# Arduino_UNO_schematic.net
KiCad netlist of a schematic drawn in Altium Designer
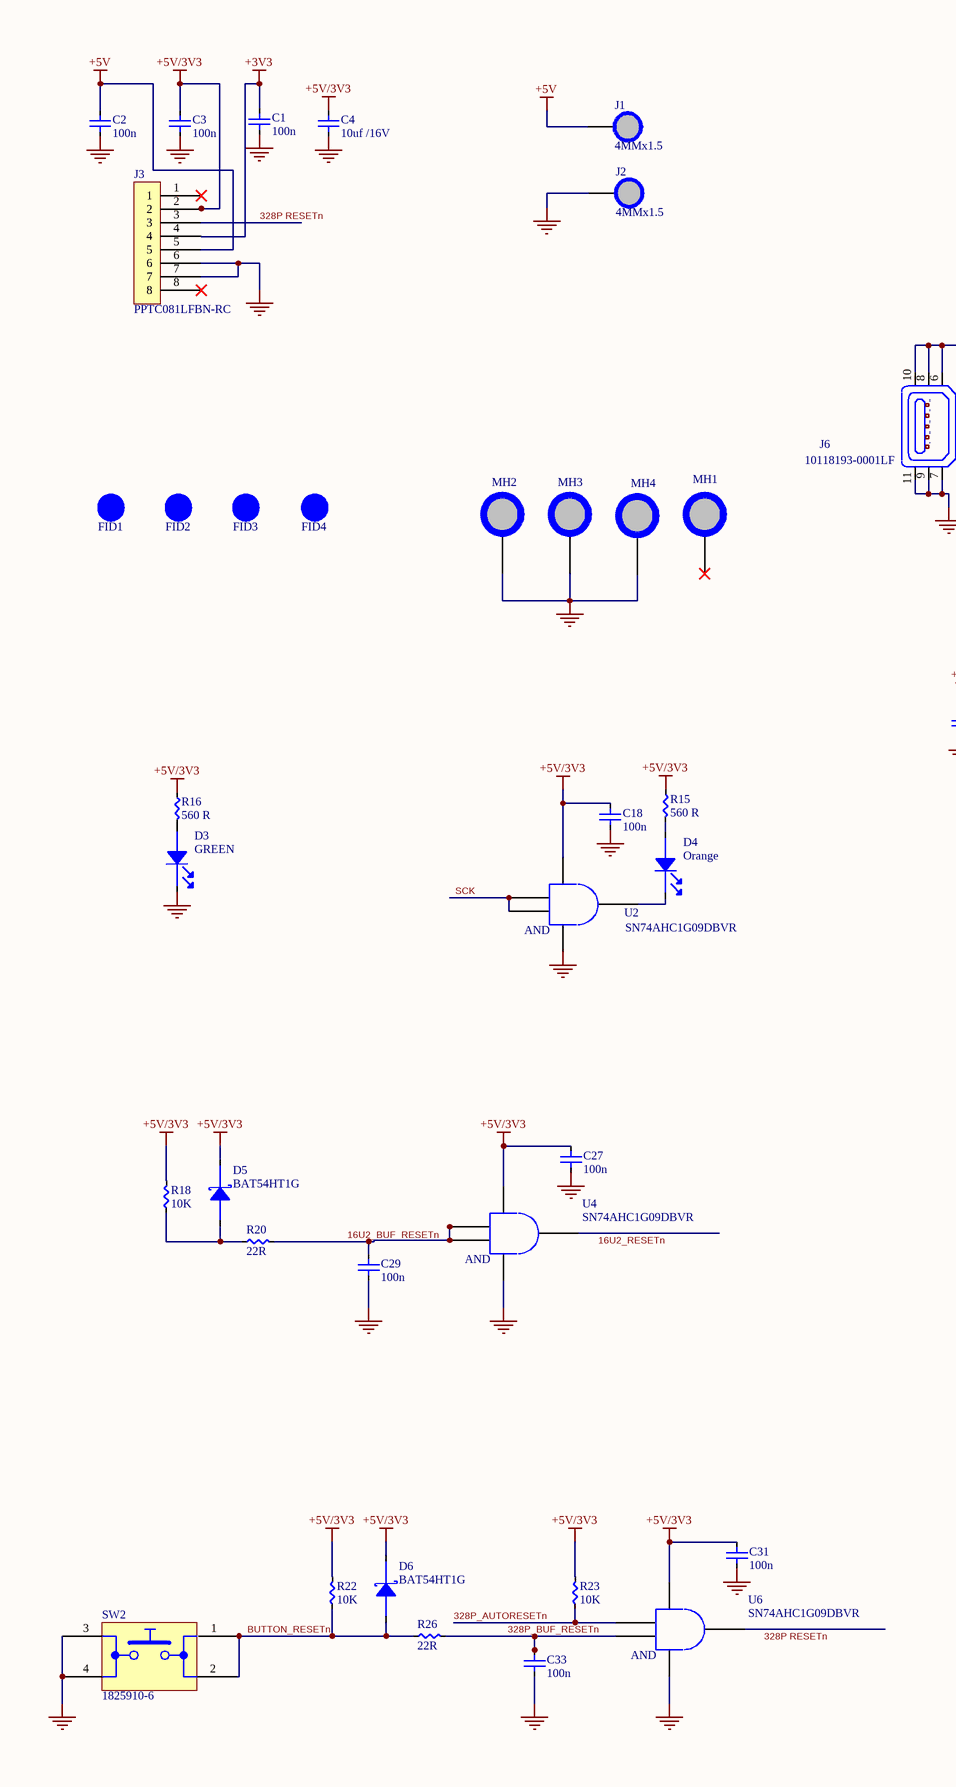
[diagram p0: Arduino_UNO_schematic.SchDoc, left]
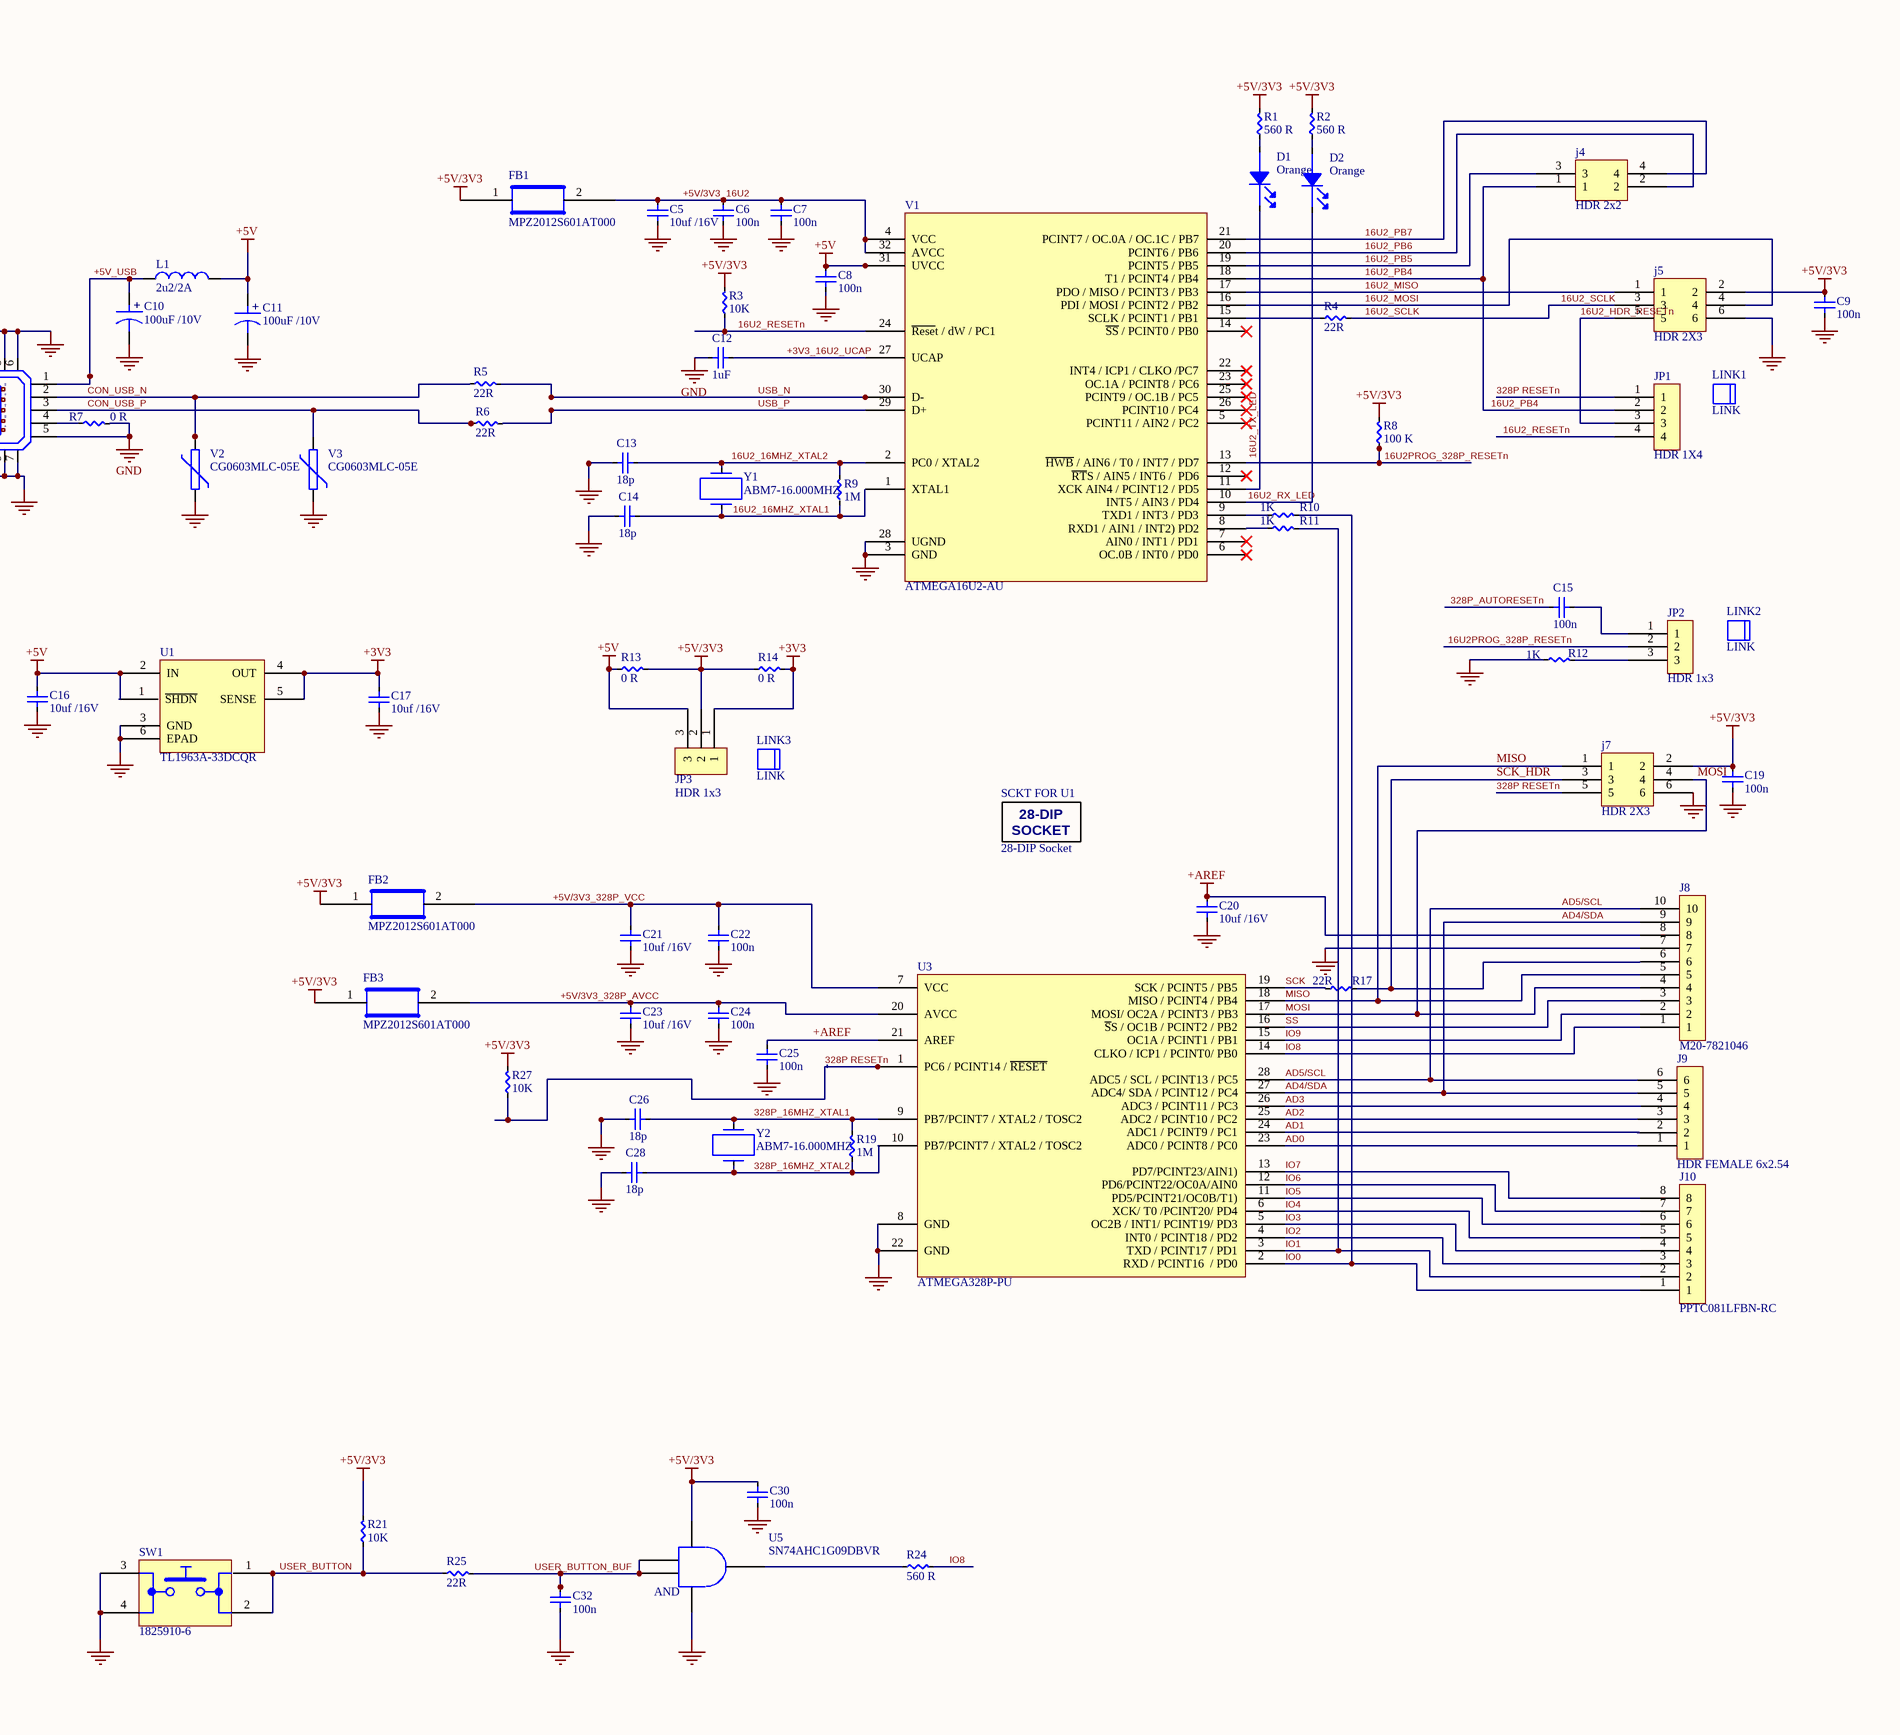
[diagram p1: Arduino_UNO_schematic.SchDoc, right]

(export (version "E")
  (design (tool "Eeschema 10.0.6"))
  (components
    (comp (ref "C1")
      (value "100n")
      (footprint "C805")
      (description "Cap Ceramic 0.1uF 50V X7R 20% SMD 0805 125°C Punched Paper T/R")
      (fields (field (name "TOLERANCE") "20%") (field (name "MANUFACTURER") "KEMET"))
      (libsource (lib "Arduino_UNO_Schematic_lib") (part "C0805C104M5RACAUTO"))
    )
    (comp (ref "C2")
      (value "100n")
      (footprint "C805")
      (description "Cap Ceramic 0.1uF 50V X7R 20% SMD 0805 125°C Punched Paper T/R")
      (fields (field (name "TOLERANCE") "20%") (field (name "MANUFACTURER") "KEMET"))
      (libsource (lib "Arduino_UNO_Schematic_lib") (part "C0805C104M5RACAUTO"))
    )
    (comp (ref "C3")
      (value "100n")
      (footprint "C805")
      (description "Cap Ceramic 0.1uF 50V X7R 20% SMD 0805 125°C Punched Paper T/R")
      (fields (field (name "TOLERANCE") "20%") (field (name "MANUFACTURER") "KEMET"))
      (libsource (lib "Arduino_UNO_Schematic_lib") (part "C0805C104M5RACAUTO"))
    )
    (comp (ref "C4")
      (value "10uf /16V")
      (footprint "C805-10Uf")
      (description "TDK - CGA4J1X7S1C106K125AC - CGA4J1X7S1C106KT000N")
      (fields
        (field (name "TOLERANCE") "10%")
        (field (name "MANUFACTURER PART NUMBER") "CGA4J1X7S1C106K125AC")
      )
      (libsource (lib "Arduino_UNO_Schematic_lib") (part "CGA4J1X7S1C106K125AC"))
    )
    (comp (ref "C5")
      (value "10uf /16V")
      (footprint "C805-10Uf")
      (description "TDK - CGA4J1X7S1C106K125AC - CGA4J1X7S1C106KT000N")
      (fields
        (field (name "TOLERANCE") "10%")
        (field (name "MANUFACTURER PART NUMBER") "CGA4J1X7S1C106K125AC")
      )
      (libsource (lib "Arduino_UNO_Schematic_lib") (part "CGA4J1X7S1C106K125AC"))
    )
    (comp (ref "C6")
      (value "100n")
      (footprint "C805")
      (description "Cap Ceramic 0.1uF 50V X7R 20% SMD 0805 125°C Punched Paper T/R")
      (fields (field (name "TOLERANCE") "20%") (field (name "MANUFACTURER") "KEMET"))
      (libsource (lib "Arduino_UNO_Schematic_lib") (part "C0805C104M5RACAUTO"))
    )
    (comp (ref "C7")
      (value "100n")
      (footprint "C805")
      (description "Cap Ceramic 0.1uF 50V X7R 20% SMD 0805 125°C Punched Paper T/R")
      (fields (field (name "TOLERANCE") "20%") (field (name "MANUFACTURER") "KEMET"))
      (libsource (lib "Arduino_UNO_Schematic_lib") (part "C0805C104M5RACAUTO"))
    )
    (comp (ref "C8")
      (value "100n")
      (footprint "C805")
      (description "Cap Ceramic 0.1uF 50V X7R 20% SMD 0805 125°C Punched Paper T/R")
      (fields (field (name "TOLERANCE") "20%") (field (name "MANUFACTURER") "KEMET"))
      (libsource (lib "Arduino_UNO_Schematic_lib") (part "C0805C104M5RACAUTO"))
    )
    (comp (ref "C9")
      (value "100n")
      (footprint "C805")
      (description "Cap Ceramic 0.1uF 50V X7R 20% SMD 0805 125°C Punched Paper T/R")
      (fields (field (name "TOLERANCE") "20%") (field (name "MANUFACTURER") "KEMET"))
      (libsource (lib "Arduino_UNO_Schematic_lib") (part "C0805C104M5RACAUTO"))
    )
    (comp (ref "C10")
      (value "100uF /10V")
      (footprint "C_ALUMI_100")
      (description "GLOVE, POLYAMIDE, L/FREE, PU, SIZE 6 - More Details")
      (fields (field (name "TOLERANCE") "20%") (field (name "VOLTAGE") "10V"))
      (libsource (lib "Arduino_UNO_Schematic_lib") (part "EEE-1AA101SP"))
    )
    (comp (ref "C11")
      (value "100uF /10V")
      (footprint "C_ALUMI_100")
      (description "GLOVE, POLYAMIDE, L/FREE, PU, SIZE 6 - More Details")
      (fields (field (name "TOLERANCE") "20%") (field (name "VOLTAGE") "10V"))
      (libsource (lib "Arduino_UNO_Schematic_lib") (part "EEE-1AA101SP"))
    )
    (comp (ref "C12")
      (value "1uF")
      (footprint "C805")
      (fields
        (field (name "TOLERANCE") "10%")
        (field (name "VOLTAGE") "25V")
        (field (name "MANUFACTURER") "TDK")
      )
      (libsource (lib "Arduino_UNO_Schematic_lib") (part "C2012X5R1E105K125AA"))
    )
    (comp (ref "C13")
      (value "18p")
      (footprint "C805")
      (description "CAP CER 18PF 50V C0G/NP0 0805")
      (fields (field (name "TOLERANCE") "5%") (field (name "VOLTAGE") "50V"))
      (libsource (lib "Arduino_UNO_Schematic_lib") (part "C0805C180J5GACTU"))
    )
    (comp (ref "C14")
      (value "18p")
      (footprint "C805")
      (description "CAP CER 18PF 50V C0G/NP0 0805")
      (fields (field (name "TOLERANCE") "5%") (field (name "VOLTAGE") "50V"))
      (libsource (lib "Arduino_UNO_Schematic_lib") (part "C0805C180J5GACTU"))
    )
    (comp (ref "C15")
      (value "100n")
      (footprint "C805")
      (description "Cap Ceramic 0.1uF 50V X7R 20% SMD 0805 125°C Punched Paper T/R")
      (fields (field (name "TOLERANCE") "20%") (field (name "MANUFACTURER") "KEMET"))
      (libsource (lib "Arduino_UNO_Schematic_lib") (part "C0805C104M5RACAUTO"))
    )
    (comp (ref "C16")
      (value "10uf /16V")
      (footprint "C805-10Uf")
      (description "TDK - CGA4J1X7S1C106K125AC - CGA4J1X7S1C106KT000N")
      (fields
        (field (name "TOLERANCE") "10%")
        (field (name "MANUFACTURER PART NUMBER") "CGA4J1X7S1C106K125AC")
      )
      (libsource (lib "Arduino_UNO_Schematic_lib") (part "CGA4J1X7S1C106K125AC"))
    )
    (comp (ref "C17")
      (value "10uf /16V")
      (footprint "C805-10Uf")
      (description "TDK - CGA4J1X7S1C106K125AC - CGA4J1X7S1C106KT000N")
      (fields
        (field (name "TOLERANCE") "10%")
        (field (name "MANUFACTURER PART NUMBER") "CGA4J1X7S1C106K125AC")
      )
      (libsource (lib "Arduino_UNO_Schematic_lib") (part "CGA4J1X7S1C106K125AC"))
    )
    (comp (ref "C18")
      (value "100n")
      (footprint "C805")
      (description "Cap Ceramic 0.1uF 50V X7R 20% SMD 0805 125°C Punched Paper T/R")
      (fields (field (name "TOLERANCE") "20%") (field (name "MANUFACTURER") "KEMET"))
      (libsource (lib "Arduino_UNO_Schematic_lib") (part "C0805C104M5RACAUTO"))
    )
    (comp (ref "C19")
      (value "100n")
      (footprint "C805")
      (description "Cap Ceramic 0.1uF 50V X7R 20% SMD 0805 125°C Punched Paper T/R")
      (fields (field (name "TOLERANCE") "20%") (field (name "MANUFACTURER") "KEMET"))
      (libsource (lib "Arduino_UNO_Schematic_lib") (part "C0805C104M5RACAUTO"))
    )
    (comp (ref "C20")
      (value "10uf /16V")
      (footprint "C805-10Uf")
      (description "TDK - CGA4J1X7S1C106K125AC - CGA4J1X7S1C106KT000N")
      (fields
        (field (name "TOLERANCE") "10%")
        (field (name "MANUFACTURER PART NUMBER") "CGA4J1X7S1C106K125AC")
      )
      (libsource (lib "Arduino_UNO_Schematic_lib") (part "CGA4J1X7S1C106K125AC"))
    )
    (comp (ref "C21")
      (value "10uf /16V")
      (footprint "C805-10Uf")
      (description "TDK - CGA4J1X7S1C106K125AC - CGA4J1X7S1C106KT000N")
      (fields
        (field (name "TOLERANCE") "10%")
        (field (name "MANUFACTURER PART NUMBER") "CGA4J1X7S1C106K125AC")
      )
      (libsource (lib "Arduino_UNO_Schematic_lib") (part "CGA4J1X7S1C106K125AC"))
    )
    (comp (ref "C22")
      (value "100n")
      (footprint "C805")
      (description "Cap Ceramic 0.1uF 50V X7R 20% SMD 0805 125°C Punched Paper T/R")
      (fields (field (name "TOLERANCE") "20%") (field (name "MANUFACTURER") "KEMET"))
      (libsource (lib "Arduino_UNO_Schematic_lib") (part "C0805C104M5RACAUTO"))
    )
    (comp (ref "C23")
      (value "10uf /16V")
      (footprint "C805-10Uf")
      (description "TDK - CGA4J1X7S1C106K125AC - CGA4J1X7S1C106KT000N")
      (fields
        (field (name "TOLERANCE") "10%")
        (field (name "MANUFACTURER PART NUMBER") "CGA4J1X7S1C106K125AC")
      )
      (libsource (lib "Arduino_UNO_Schematic_lib") (part "CGA4J1X7S1C106K125AC"))
    )
    (comp (ref "C24")
      (value "100n")
      (footprint "C805")
      (description "Cap Ceramic 0.1uF 50V X7R 20% SMD 0805 125°C Punched Paper T/R")
      (fields (field (name "TOLERANCE") "20%") (field (name "MANUFACTURER") "KEMET"))
      (libsource (lib "Arduino_UNO_Schematic_lib") (part "C0805C104M5RACAUTO"))
    )
    (comp (ref "C25")
      (value "100n")
      (footprint "C805")
      (description "Cap Ceramic 0.1uF 50V X7R 20% SMD 0805 125°C Punched Paper T/R")
      (fields (field (name "TOLERANCE") "20%") (field (name "MANUFACTURER") "KEMET"))
      (libsource (lib "Arduino_UNO_Schematic_lib") (part "C0805C104M5RACAUTO"))
    )
    (comp (ref "C26")
      (value "18p")
      (footprint "C805")
      (description "CAP CER 18PF 50V C0G/NP0 0805")
      (fields (field (name "TOLERANCE") "5%") (field (name "VOLTAGE") "50V"))
      (libsource (lib "Arduino_UNO_Schematic_lib") (part "C0805C180J5GACTU"))
    )
    (comp (ref "C27")
      (value "100n")
      (footprint "C805")
      (description "Cap Ceramic 0.1uF 50V X7R 20% SMD 0805 125°C Punched Paper T/R")
      (fields (field (name "TOLERANCE") "20%") (field (name "MANUFACTURER") "KEMET"))
      (libsource (lib "Arduino_UNO_Schematic_lib") (part "C0805C104M5RACAUTO"))
    )
    (comp (ref "C28")
      (value "18p")
      (footprint "C805")
      (description "CAP CER 18PF 50V C0G/NP0 0805")
      (fields (field (name "TOLERANCE") "5%") (field (name "VOLTAGE") "50V"))
      (libsource (lib "Arduino_UNO_Schematic_lib") (part "C0805C180J5GACTU"))
    )
    (comp (ref "C29")
      (value "100n")
      (footprint "C805")
      (description "Cap Ceramic 0.1uF 50V X7R 20% SMD 0805 125°C Punched Paper T/R")
      (fields (field (name "TOLERANCE") "20%") (field (name "MANUFACTURER") "KEMET"))
      (libsource (lib "Arduino_UNO_Schematic_lib") (part "C0805C104M5RACAUTO"))
    )
    (comp (ref "C30")
      (value "100n")
      (footprint "C805")
      (description "Cap Ceramic 0.1uF 50V X7R 20% SMD 0805 125°C Punched Paper T/R")
      (fields (field (name "TOLERANCE") "20%") (field (name "MANUFACTURER") "KEMET"))
      (libsource (lib "Arduino_UNO_Schematic_lib") (part "C0805C104M5RACAUTO"))
    )
    (comp (ref "C31")
      (value "100n")
      (footprint "C805")
      (description "Cap Ceramic 0.1uF 50V X7R 20% SMD 0805 125°C Punched Paper T/R")
      (fields (field (name "TOLERANCE") "20%") (field (name "MANUFACTURER") "KEMET"))
      (libsource (lib "Arduino_UNO_Schematic_lib") (part "C0805C104M5RACAUTO"))
    )
    (comp (ref "C32")
      (value "100n")
      (footprint "C805")
      (description "Cap Ceramic 0.1uF 50V X7R 20% SMD 0805 125°C Punched Paper T/R")
      (fields (field (name "TOLERANCE") "20%") (field (name "MANUFACTURER") "KEMET"))
      (libsource (lib "Arduino_UNO_Schematic_lib") (part "C0805C104M5RACAUTO"))
    )
    (comp (ref "C33")
      (value "100n")
      (footprint "C805")
      (description "Cap Ceramic 0.1uF 50V X7R 20% SMD 0805 125°C Punched Paper T/R")
      (fields (field (name "TOLERANCE") "20%") (field (name "MANUFACTURER") "KEMET"))
      (libsource (lib "Arduino_UNO_Schematic_lib") (part "C0805C104M5RACAUTO"))
    )
    (comp (ref "D1")
      (value "Orange")
      (footprint "LED_0603")
      (description "OSRAM - LO L29K-H2K1-24-Z - SMARTLED 0603 ORANGE")
      (fields
        (field (name "MANUFACTURER") "Osram Opto")
        (field (name "MANUFACTURER PART NUMBER") "LOL29K-H2K1-24-Z")
      )
      (libsource (lib "Arduino_UNO_Schematic_lib") (part "LOL29K-H2K1-24-Z"))
    )
    (comp (ref "D2")
      (value "Orange")
      (footprint "LED_0603")
      (description "OSRAM - LO L29K-H2K1-24-Z - SMARTLED 0603 ORANGE")
      (fields
        (field (name "MANUFACTURER") "Osram Opto")
        (field (name "MANUFACTURER PART NUMBER") "LOL29K-H2K1-24-Z")
      )
      (libsource (lib "Arduino_UNO_Schematic_lib") (part "LOL29K-H2K1-24-Z"))
    )
    (comp (ref "D3")
      (value "GREEN")
      (footprint "LED_0603")
      (description "LED Uni-Color Green 572nm 2-Pin Chip 0603(1608Metric) T/R")
      (fields
        (field (name "MANUFACTURER") "Osram Opto")
        (field (name "MANUFACTURER PART NUMBER") "LGL29K-G2J1-24-Z")
      )
      (libsource (lib "Arduino_UNO_Schematic_lib") (part "LGL29K-G2J1-24-Z"))
    )
    (comp (ref "D4")
      (value "Orange")
      (footprint "LED_0603")
      (description "OSRAM - LO L29K-H2K1-24-Z - SMARTLED 0603 ORANGE")
      (fields
        (field (name "MANUFACTURER") "Osram Opto")
        (field (name "MANUFACTURER PART NUMBER") "LOL29K-H2K1-24-Z")
      )
      (libsource (lib "Arduino_UNO_Schematic_lib") (part "LOL29K-H2K1-24-Z"))
    )
    (comp (ref "D5")
      (value "BAT54HT1G")
      (footprint "SO-232")
      (description "Small Signal Schottky Diode, Single, 30 V, 200 mA, 800 mV, 600 mA, 150 C ;RoHS Compliant: Yes")
      (fields (field (name "MANUFACTURER") "ON Semiconductor / Fairchild"))
      (libsource (lib "Arduino_UNO_Schematic_lib") (part "BAT54HT1G"))
    )
    (comp (ref "D6")
      (value "BAT54HT1G")
      (footprint "SO-232")
      (description "Small Signal Schottky Diode, Single, 30 V, 200 mA, 800 mV, 600 mA, 150 C ;RoHS Compliant: Yes")
      (fields (field (name "MANUFACTURER") "ON Semiconductor / Fairchild"))
      (libsource (lib "Arduino_UNO_Schematic_lib") (part "BAT54HT1G"))
    )
    (comp (ref "FB1")
      (value "MPZ2012S601AT000")
      (footprint "C805")
      (description "FERRITE BEAD 600 OHM 0805 1LN")
      (fields (field (name "MANUFACTURER") "TDK"))
      (libsource (lib "Arduino_UNO_Schematic_lib") (part "MPZ2012S601AT000"))
    )
    (comp (ref "FB2")
      (value "MPZ2012S601AT000")
      (footprint "C805")
      (description "FERRITE BEAD 600 OHM 0805 1LN")
      (fields (field (name "MANUFACTURER") "TDK"))
      (libsource (lib "Arduino_UNO_Schematic_lib") (part "MPZ2012S601AT000"))
    )
    (comp (ref "FB3")
      (value "MPZ2012S601AT000")
      (footprint "C805")
      (description "FERRITE BEAD 600 OHM 0805 1LN")
      (fields (field (name "MANUFACTURER") "TDK"))
      (libsource (lib "Arduino_UNO_Schematic_lib") (part "MPZ2012S601AT000"))
    )
    (comp (ref "FID1")
      (value "FID_1MMC")
      (footprint "FID_40x120D")
      (libsource (lib "Arduino_UNO_Schematic_lib") (part "FID_1MM"))
    )
    (comp (ref "FID2")
      (value "FID_1MMC")
      (footprint "FID_40x120D")
      (libsource (lib "Arduino_UNO_Schematic_lib") (part "FID_1MM"))
    )
    (comp (ref "FID3")
      (value "FID_1MMC")
      (footprint "FID_40x120D")
      (libsource (lib "Arduino_UNO_Schematic_lib") (part "FID_1MM"))
    )
    (comp (ref "FID4")
      (value "FID_1MMC")
      (footprint "FID_40x120D")
      (libsource (lib "Arduino_UNO_Schematic_lib") (part "FID_1MM"))
    )
    (comp (ref "J1")
      (value "4MMx1.5")
      (footprint "PAD_WITH_HOLE_1.44MM")
      (libsource (lib "Arduino_UNO_Schematic_lib") (part "PAD_WITH_HOLE_4MMx1.5MM"))
    )
    (comp (ref "J2")
      (value "4MMx1.5")
      (footprint "PAD_WITH_HOLE_1.44MM")
      (libsource (lib "Arduino_UNO_Schematic_lib") (part "PAD_WITH_HOLE_4MMx1.5MM"))
    )
    (comp (ref "J3")
      (value "PPTC081LFBN-RC")
      (footprint "HDR FEMALE 8x2.54")
      (description "CONN HDR 8POS 0.1 TIN PCB")
      (fields (field (name "MANUFACTURER") "Sullins"))
      (libsource (lib "altium-import") (part "root_0_mirrored_PPTC081LFBN-RC_"))
    )
    (comp (ref "j4")
      (value "HDR 2x2")
      (footprint "HDR 2x2_2.54mm")
      (description "02+02 DIL Vert Pin Hdr")
      (fields (field (name "MANUFACTURER") "Harwin") (field (name "MANUFACTURER PART NUMBER") "M20-9980245"))
      (libsource (lib "Arduino_UNO_Schematic_lib") (part "M20-9980245"))
    )
    (comp (ref "j5")
      (value "HDR 2X3")
      (footprint "HDR 2x3")
      (description "Headers & Wire Housings 03+03 DIL VERTICAL PIN HEADER GOLD+TIN")
      (fields (field (name "MANUFACTURER") "Harwin") (field (name "MANUFACTURER PART NUMBER") "M20-9760342"))
      (libsource (lib "Arduino_UNO_Schematic_lib") (part "M20-9760342"))
    )
    (comp (ref "J6")
      (value "10118193-0001LF")
      (footprint "10118193")
      (description "CONN USB MICRO B RECPT SMT R/A")
      (fields (field (name "MANUFACTURER") "Amphenol FCI"))
      (libsource (lib "Arduino_UNO_Schematic_lib") (part "10118193-0001LF"))
    )
    (comp (ref "j7")
      (value "HDR 2X3")
      (footprint "HDR 2x3")
      (description "Headers & Wire Housings 03+03 DIL VERTICAL PIN HEADER GOLD+TIN")
      (fields (field (name "MANUFACTURER") "Harwin") (field (name "MANUFACTURER PART NUMBER") "M20-9760342"))
      (libsource (lib "Arduino_UNO_Schematic_lib") (part "M20-9760342"))
    )
    (comp (ref "J8")
      (value "M20-7821046")
      (footprint "HDR FEMALE 10x2.54")
      (fields (field (name "MANUFACTURER") "Harwin"))
      (libsource (lib "altium-import") (part "root_2_mirrored_HDR FEMALE 10x2.54_"))
    )
    (comp (ref "J9")
      (value "HDR FEMALE 6x2.54")
      (footprint "HDR FEMALE 6x2.54")
      (description "Female, 6 C, Straight, .100\"CC; 3.20mm Tail, No Mt. 100u\" Tin; PBT, Phos Bronze, 105 C")
      (fields
        (field (name "MANUFACTURER") "Sullins")
        (field (name "MANUFACTURER PART NUMBER") "PPTC061LFBN-RC")
      )
      (libsource (lib "Arduino_UNO_Schematic_lib") (part "HDR FEMALE 6x2.54"))
    )
    (comp (ref "J10")
      (value "PPTC081LFBN-RC")
      (footprint "HDR FEMALE 8x2.54")
      (description "CONN HDR 8POS 0.1 TIN PCB")
      (fields (field (name "MANUFACTURER") "Sullins"))
      (libsource (lib "altium-import") (part "root_2_mirrored_PPTC081LFBN-RC_"))
    )
    (comp (ref "JP1")
      (value "HDR 1X4")
      (footprint "HDR MALE 1X4_2.54")
      (fields (field (name "MANUFACTURER") "Harwin") (field (name "MANUFACTURER PART NUMBER") "M20-9990445"))
      (libsource (lib "Arduino_UNO_Schematic_lib") (part "M20-9990445"))
    )
    (comp (ref "JP2")
      (value "HDR 1x3")
      (footprint "HDR_1x3x2.54")
      (fields (field (name "MANUFACTURER") "Harwin") (field (name "MANUFACTURER PART NUMBER") "M20-9990345"))
      (libsource (lib "Arduino_UNO_Schematic_lib") (part "M20-9990345"))
    )
    (comp (ref "JP3")
      (value "HDR 1x3")
      (footprint "HDR_1x3x2.54")
      (fields (field (name "MANUFACTURER") "Harwin") (field (name "MANUFACTURER PART NUMBER") "M20-9990345"))
      (libsource (lib "") (part "M20-9990345_1"))
    )
    (comp (ref "L1")
      (value "2u2/2A")
      (footprint "C1210_IND")
      (description "FIXED IND 2.2UH 2A 80 MOHM SMD")
      (fields (field (name "TOLERANCE") "20%") (field (name "MANUFACTURER") "KEMET"))
      (libsource (lib "Arduino_UNO_Schematic_lib") (part "L1210R2R2MDWIT"))
    )
    (comp (ref "LINK1")
      (value "LINK")
      (description "CONN JUMPER SHORTING TIN")
      (fields (field (name "MANUFACTURER") "Sullins") (field (name "MANUFACTURER PART NUMBER") "STC02SYAN"))
      (libsource (lib "Arduino_UNO_Schematic_lib") (part "STC02SYAN"))
    )
    (comp (ref "LINK2")
      (value "LINK")
      (description "CONN JUMPER SHORTING TIN")
      (fields (field (name "MANUFACTURER") "Sullins") (field (name "MANUFACTURER PART NUMBER") "STC02SYAN"))
      (libsource (lib "Arduino_UNO_Schematic_lib") (part "STC02SYAN"))
    )
    (comp (ref "LINK3")
      (value "LINK")
      (description "CONN JUMPER SHORTING TIN")
      (fields (field (name "MANUFACTURER") "Sullins") (field (name "MANUFACTURER PART NUMBER") "STC02SYAN"))
      (libsource (lib "Arduino_UNO_Schematic_lib") (part "STC02SYAN"))
    )
    (comp (ref "MH1")
      (value "MH_7.4MMNC_3.2MMD")
      (footprint "MH_7.4MMD_3.2MM_NO_COPPER_NPTH")
      (libsource (lib "Arduino_UNO_Schematic_lib") (part "MH_7.4MMNC_3.2MMD"))
    )
    (comp (ref "MH2")
      (value "MH_7.4MMC_3.2MMd")
      (footprint "MH_7.4MMD_3.2MMD")
      (libsource (lib "Arduino_UNO_Schematic_lib") (part "MH_7.4MMC_3.2MMD"))
    )
    (comp (ref "MH3")
      (value "MH_7.4MMC_3.2MMd")
      (footprint "MH_7.4MMD_3.2MMD")
      (libsource (lib "Arduino_UNO_Schematic_lib") (part "MH_7.4MMC_3.2MMD"))
    )
    (comp (ref "MH4")
      (value "MH_7.4MMC_3.2MMd")
      (footprint "MH_7.4MMD_3.2MMD")
      (libsource (lib "Arduino_UNO_Schematic_lib") (part "MH_7.4MMC_3.2MMD"))
    )
    (comp (ref "R1")
      (value "560 R")
      (footprint "R0805")
      (description "Surface Mount Thick Film Resistor, RC Series, 560 ohm, 125 mW, - 1%, 150 V, 0805 [2012 Metric]")
      (fields (field (name "TOLERANCE") "1%") (field (name "MANUFACTURER") "Yageo"))
      (libsource (lib "") (part "RC0805FR-07560RL_2"))
    )
    (comp (ref "R2")
      (value "560 R")
      (footprint "R0805")
      (description "Surface Mount Thick Film Resistor, RC Series, 560 ohm, 125 mW, - 1%, 150 V, 0805 [2012 Metric]")
      (fields (field (name "TOLERANCE") "1%") (field (name "MANUFACTURER") "Yageo"))
      (libsource (lib "") (part "RC0805FR-07560RL_2"))
    )
    (comp (ref "R3")
      (value "10K")
      (footprint "R0805")
      (description "Res Thin Film 0805 10K Ohm 1% 0.125W(1/8W) ±50ppm/C Epoxy Pad SMD T/R")
      (fields (field (name "TOLERANCE") "1%") (field (name "MANUFACTURER") "Yageo"))
      (libsource (lib "") (part "RT0805FRE0710KL_1"))
    )
    (comp (ref "R4")
      (value "22R")
      (footprint "R0805")
      (description "RES SMD 22 OHM 1% 1/8W 0805")
      (fields (field (name "TOLERANCE") "1%") (field (name "MANUFACTURER") "Yageo"))
      (libsource (lib "Arduino_UNO_Schematic_lib") (part "RC0805FR-0722RL"))
    )
    (comp (ref "R5")
      (value "22R")
      (footprint "R0805")
      (description "RES SMD 22 OHM 1% 1/8W 0805")
      (fields (field (name "TOLERANCE") "1%") (field (name "MANUFACTURER") "Yageo"))
      (libsource (lib "Arduino_UNO_Schematic_lib") (part "RC0805FR-0722RL"))
    )
    (comp (ref "R6")
      (value "22R")
      (footprint "R0805")
      (description "RES SMD 22 OHM 1% 1/8W 0805")
      (fields (field (name "TOLERANCE") "1%") (field (name "MANUFACTURER") "Yageo"))
      (libsource (lib "") (part "RC0805FR-0722RL_1"))
    )
    (comp (ref "R7")
      (value "0 R")
      (footprint "R0805")
      (description "Surface Mount Thick Film Resistor, RC Series, 125 mW, - 5%, 150 V, 0805 [2012 Metric]")
      (fields (field (name "TOLERANCE") "5%") (field (name "MANUFACTURER") "Yageo"))
      (libsource (lib "Arduino_UNO_Schematic_lib") (part "RC0805JR-070RL"))
    )
    (comp (ref "R8")
      (value "100 K")
      (footprint "R0805")
      (description "YAGEO         RC0805FR-07100KL            RES, THICK FILM, 100K, 1%, 0.125W, 0805, REEL")
      (fields (field (name "TOLERANCE") "1%") (field (name "MANUFACTURER") "Yageo"))
      (libsource (lib "Arduino_UNO_Schematic_lib") (part "RC0805FR-07100KL"))
    )
    (comp (ref "R9")
      (value "1M")
      (footprint "R0805")
      (description "RESISTOR, 0805, 1% 50PPM 1M")
      (fields (field (name "TOLERANCE") "1%") (field (name "MANUFACTURER") "Yageo"))
      (libsource (lib "") (part "RT0805FRE071ML_1"))
    )
    (comp (ref "R10")
      (value "1K")
      (footprint "R0805")
      (description "RES SMD 1K OHM 1% 1/8W 0805")
      (fields (field (name "TOLERANCE") "1%") (field (name "MANUFACTURER") "Yageo"))
      (libsource (lib "Arduino_UNO_Schematic_lib") (part "RT0805FRE071KL"))
    )
    (comp (ref "R11")
      (value "1K")
      (footprint "R0805")
      (description "RES SMD 1K OHM 1% 1/8W 0805")
      (fields (field (name "TOLERANCE") "1%") (field (name "MANUFACTURER") "Yageo"))
      (libsource (lib "Arduino_UNO_Schematic_lib") (part "RT0805FRE071KL"))
    )
    (comp (ref "R12")
      (value "1K")
      (footprint "R0805")
      (description "RES SMD 1K OHM 1% 1/8W 0805")
      (fields (field (name "TOLERANCE") "1%") (field (name "MANUFACTURER") "Yageo"))
      (libsource (lib "Arduino_UNO_Schematic_lib") (part "RT0805FRE071KL"))
    )
    (comp (ref "R13")
      (value "0 R")
      (footprint "R0805")
      (description "Surface Mount Thick Film Resistor, RC Series, 125 mW, - 5%, 150 V, 0805 [2012 Metric]")
      (fields (field (name "TOLERANCE") "5%") (field (name "MANUFACTURER") "Yageo"))
      (libsource (lib "") (part "RC0805JR-070RL_1"))
    )
    (comp (ref "R14")
      (value "0 R")
      (footprint "R0805")
      (description "Surface Mount Thick Film Resistor, RC Series, 125 mW, - 5%, 150 V, 0805 [2012 Metric]")
      (fields (field (name "TOLERANCE") "5%") (field (name "MANUFACTURER") "Yageo"))
      (libsource (lib "Arduino_UNO_Schematic_lib") (part "RC0805JR-070RL"))
    )
    (comp (ref "R15")
      (value "560 R")
      (footprint "R0805")
      (description "Surface Mount Thick Film Resistor, RC Series, 560 ohm, 125 mW, - 1%, 150 V, 0805 [2012 Metric]")
      (fields (field (name "TOLERANCE") "1%") (field (name "MANUFACTURER") "Yageo"))
      (libsource (lib "") (part "RC0805FR-07560RL_1"))
    )
    (comp (ref "R16")
      (value "560 R")
      (footprint "R0805")
      (description "Surface Mount Thick Film Resistor, RC Series, 560 ohm, 125 mW, - 1%, 150 V, 0805 [2012 Metric]")
      (fields (field (name "TOLERANCE") "1%") (field (name "MANUFACTURER") "Yageo"))
      (libsource (lib "") (part "RC0805FR-07560RL_1"))
    )
    (comp (ref "R17")
      (value "22R")
      (footprint "R0805")
      (description "RES SMD 22 OHM 1% 1/8W 0805")
      (fields (field (name "TOLERANCE") "1%") (field (name "MANUFACTURER") "Yageo"))
      (libsource (lib "") (part "RC0805FR-0722RL_1"))
    )
    (comp (ref "R18")
      (value "10K")
      (footprint "R0805")
      (description "Res Thin Film 0805 10K Ohm 1% 0.125W(1/8W) ±50ppm/C Epoxy Pad SMD T/R")
      (fields (field (name "TOLERANCE") "1%") (field (name "MANUFACTURER") "Yageo"))
      (libsource (lib "") (part "RT0805FRE0710KL_1"))
    )
    (comp (ref "R19")
      (value "1M")
      (footprint "R0805")
      (description "RESISTOR, 0805, 1% 50PPM 1M")
      (fields (field (name "TOLERANCE") "1%") (field (name "MANUFACTURER") "Yageo"))
      (libsource (lib "Arduino_UNO_Schematic_lib") (part "RT0805FRE071ML"))
    )
    (comp (ref "R20")
      (value "22R")
      (footprint "R0805")
      (description "RES SMD 22 OHM 1% 1/8W 0805")
      (fields (field (name "TOLERANCE") "1%") (field (name "MANUFACTURER") "Yageo"))
      (libsource (lib "") (part "RC0805FR-0722RL_1"))
    )
    (comp (ref "R21")
      (value "10K")
      (footprint "R0805")
      (description "Res Thin Film 0805 10K Ohm 1% 0.125W(1/8W) ±50ppm/C Epoxy Pad SMD T/R")
      (fields (field (name "TOLERANCE") "1%") (field (name "MANUFACTURER") "Yageo"))
      (libsource (lib "Arduino_UNO_Schematic_lib") (part "RT0805FRE0710KL"))
    )
    (comp (ref "R22")
      (value "10K")
      (footprint "R0805")
      (description "Res Thin Film 0805 10K Ohm 1% 0.125W(1/8W) ±50ppm/C Epoxy Pad SMD T/R")
      (fields (field (name "TOLERANCE") "1%") (field (name "MANUFACTURER") "Yageo"))
      (libsource (lib "") (part "RT0805FRE0710KL_1"))
    )
    (comp (ref "R23")
      (value "10K")
      (footprint "R0805")
      (description "Res Thin Film 0805 10K Ohm 1% 0.125W(1/8W) ±50ppm/C Epoxy Pad SMD T/R")
      (fields (field (name "TOLERANCE") "1%") (field (name "MANUFACTURER") "Yageo"))
      (libsource (lib "") (part "RT0805FRE0710KL_1"))
    )
    (comp (ref "R24")
      (value "560 R")
      (footprint "R0805")
      (description "Surface Mount Thick Film Resistor, RC Series, 560 ohm, 125 mW, - 1%, 150 V, 0805 [2012 Metric]")
      (fields (field (name "TOLERANCE") "1%") (field (name "MANUFACTURER") "Yageo"))
      (libsource (lib "Arduino_UNO_Schematic_lib") (part "RC0805FR-07560RL"))
    )
    (comp (ref "R25")
      (value "22R")
      (footprint "R0805")
      (description "RES SMD 22 OHM 1% 1/8W 0805")
      (fields (field (name "TOLERANCE") "1%") (field (name "MANUFACTURER") "Yageo"))
      (libsource (lib "") (part "RC0805FR-0722RL_2"))
    )
    (comp (ref "R26")
      (value "22R")
      (footprint "R0805")
      (description "RES SMD 22 OHM 1% 1/8W 0805")
      (fields (field (name "TOLERANCE") "1%") (field (name "MANUFACTURER") "Yageo"))
      (libsource (lib "") (part "RC0805FR-0722RL_1"))
    )
    (comp (ref "R27")
      (value "10K")
      (footprint "R0805")
      (description "Res Thin Film 0805 10K Ohm 1% 0.125W(1/8W) ±50ppm/C Epoxy Pad SMD T/R")
      (fields (field (name "TOLERANCE") "1%") (field (name "MANUFACTURER") "Yageo"))
      (libsource (lib "") (part "RT0805FRE0710KL_2"))
    )
    (comp (ref "SCKT FOR U1")
      (value "28-DIP Socket")
      (footprint "28_DIP_7.62mm_SOCKET")
      (description "CONN IC DIP SOCKET 28POS TIN")
      (fields (field (name "MANUFACTURER") "3M") (field (name "MANUFACTURER PART NUMBER") "4828-3004-CP"))
      (libsource (lib "altium-import") (part "root_0_4828-3004-CP (2)_"))
    )
    (comp (ref "SW1")
      (value "1825910-6")
      (footprint "1825910-6")
      (description "SWITCH TACTILE SPST-NO 0.05A 24V")
      (fields (field (name "MANUFACTURER") "TE Connectivity Alcoswitch"))
      (libsource (lib "Arduino_UNO_Schematic_lib") (part "1825910-6"))
    )
    (comp (ref "SW2")
      (value "1825910-6")
      (footprint "1825910-6")
      (description "SWITCH TACTILE SPST-NO 0.05A 24V")
      (fields (field (name "MANUFACTURER") "TE Connectivity Alcoswitch"))
      (libsource (lib "Arduino_UNO_Schematic_lib") (part "1825910-6"))
    )
    (comp (ref "U1")
      (value "TL1963A-33DCQR")
      (footprint "DCQ(R-PDSO-G6)")
      (description "IC REG LINEAR 3.3V 1.5A SOT223-6")
      (fields (field (name "MANUFACTURER") "Texas Instruments"))
      (libsource (lib "Arduino_UNO_Schematic_lib") (part "TL1963A-33DCQR"))
    )
    (comp (ref "U2")
      (value "SN74AHC1G09DBVR")
      (footprint "DVB_SOT_23_5")
      (description "TEXAS INSTRUMENTS - SN74AHC1G09DBVR - AND Gate, 74AHC1G09, 2 Input, 2 V to 5.5 V, SOT-23-5")
      (fields (field (name "MANUFACTURER") "Texas Instruments"))
      (libsource (lib "Arduino_UNO_Schematic_lib") (part "SN74AHC1G09DBVR"))
    )
    (comp (ref "U3")
      (value "ATMEGA328P-PU")
      (footprint "28_ATMEGA328P-PU")
      (description "ATMEGA328P-PU; 8 bit Microcontroller AVR 20MHz 1; 32kb Flash; 2kb RAM; I2C SPI 2")
      (fields (field (name "MANUFACTURER") "Microchip / Atmel"))
      (libsource (lib "altium-import") (part "root_0_ATMEGA328P-PU_"))
    )
    (comp (ref "U4")
      (value "SN74AHC1G09DBVR")
      (footprint "DVB_SOT_23_5")
      (description "TEXAS INSTRUMENTS - SN74AHC1G09DBVR - AND Gate, 74AHC1G09, 2 Input, 2 V to 5.5 V, SOT-23-5")
      (fields (field (name "MANUFACTURER") "Texas Instruments"))
      (libsource (lib "Arduino_UNO_Schematic_lib") (part "SN74AHC1G09DBVR"))
    )
    (comp (ref "U5")
      (value "SN74AHC1G09DBVR")
      (footprint "DVB_SOT_23_5")
      (description "TEXAS INSTRUMENTS - SN74AHC1G09DBVR - AND Gate, 74AHC1G09, 2 Input, 2 V to 5.5 V, SOT-23-5")
      (fields (field (name "MANUFACTURER") "Texas Instruments"))
      (libsource (lib "Arduino_UNO_Schematic_lib") (part "SN74AHC1G09DBVR"))
    )
    (comp (ref "U6")
      (value "SN74AHC1G09DBVR")
      (footprint "DVB_SOT_23_5")
      (description "TEXAS INSTRUMENTS - SN74AHC1G09DBVR - AND Gate, 74AHC1G09, 2 Input, 2 V to 5.5 V, SOT-23-5")
      (fields (field (name "MANUFACTURER") "Texas Instruments"))
      (libsource (lib "Arduino_UNO_Schematic_lib") (part "SN74AHC1G09DBVR"))
    )
    (comp (ref "V1")
      (value "ATMEGA16U2-AU")
      (footprint "TQFP_32_ATMEGA16U2")
      (description "MICROCHIP - ATMEGA16U2-AU - MCU, 8BIT, MEGAAVR, 16MHZ, TQFP-32")
      (fields (field (name "MANUFACTURER") "Microchip / Atmel"))
      (libsource (lib "Arduino_UNO_Schematic_lib") (part "ATMEGA16U2-AU"))
    )
    (comp (ref "V2")
      (value "CG0603MLC-05E")
      (footprint "R0603")
      (description "VARISTOR 0603")
      (fields (field (name "VOLTAGE") "5V") (field (name "MANUFACTURER") "Bourns"))
      (libsource (lib "Arduino_UNO_Schematic_lib") (part "CG0603MLC-05E"))
    )
    (comp (ref "V3")
      (value "CG0603MLC-05E")
      (footprint "R0603")
      (description "VARISTOR 0603")
      (fields (field (name "VOLTAGE") "5V") (field (name "MANUFACTURER") "Bourns"))
      (libsource (lib "Arduino_UNO_Schematic_lib") (part "CG0603MLC-05E"))
    )
    (comp (ref "Y1")
      (value "ABM7-16.000MHZ")
      (footprint "ABM7_v1_1_Big")
      (description "CRYSTAL 16.0000MHZ 18PF SMD")
      (fields (field (name "TOLERANCE") "20ppm") (field (name "MANUFACTURER") "Abracon"))
      (libsource (lib "Arduino_UNO_Schematic_lib") (part "ABM7-16.000MHZ-D2Y-T"))
    )
    (comp (ref "Y2")
      (value "ABM7-16.000MHZ")
      (footprint "ABM7_v1_1_Big")
      (description "CRYSTAL 16.0000MHZ 18PF SMD")
      (fields (field (name "TOLERANCE") "20ppm") (field (name "MANUFACTURER") "Abracon"))
      (libsource (lib "Arduino_UNO_Schematic_lib") (part "ABM7-16.000MHZ-D2Y-T"))
    )
  )
  (nets
    (net (code "1") (name "+3V3") (class "Default")
      (node (ref "C1") (pin "2") (pinfunction "2_2") (pintype "passive"))
      (node (ref "C17") (pin "2") (pinfunction "2_2") (pintype "passive"))
      (node (ref "J3") (pin "4") (pinfunction "4_4") (pintype "passive"))
      (node (ref "JP3") (pin "1") (pinfunction "1_1") (pintype "passive"))
      (node (ref "R14") (pin "2") (pinfunction "2_2") (pintype "passive"))
      (node (ref "U1") (pin "4") (pinfunction "OUT_4") (pintype "passive"))
      (node (ref "U1") (pin "5") (pinfunction "SENSE_5") (pintype "passive"))
    )
    (net (code "2") (name "+5V") (class "Default")
      (node (ref "C11") (pin "1") (pinfunction "1_1") (pintype "passive"))
      (node (ref "C16") (pin "2") (pinfunction "2_2") (pintype "passive"))
      (node (ref "C2") (pin "2") (pinfunction "2_2") (pintype "passive"))
      (node (ref "C8") (pin "2") (pinfunction "2_2") (pintype "passive"))
      (node (ref "J1") (pin "1") (pinfunction "_1_1") (pintype "passive"))
      (node (ref "J3") (pin "5") (pinfunction "5_5") (pintype "passive"))
      (node (ref "JP3") (pin "3") (pinfunction "3_3") (pintype "passive"))
      (node (ref "L1") (pin "2") (pinfunction "2_2") (pintype "passive"))
      (node (ref "R13") (pin "1") (pinfunction "1_1") (pintype "passive"))
      (node (ref "U1") (pin "1") (pinfunction "~{SHDN}_1") (pintype "passive"))
      (node (ref "U1") (pin "2") (pinfunction "IN_2") (pintype "passive"))
      (node (ref "V1") (pin "31") (pinfunction "UVCC_31") (pintype "passive"))
    )
    (net (code "3") (name "+5V{slash}3V3") (class "Default")
      (node (ref "C18") (pin "2") (pinfunction "2_2") (pintype "passive"))
      (node (ref "C19") (pin "2") (pinfunction "2_2") (pintype "passive"))
      (node (ref "C27") (pin "2") (pinfunction "2_2") (pintype "passive"))
      (node (ref "C3") (pin "2") (pinfunction "2_2") (pintype "passive"))
      (node (ref "C30") (pin "2") (pinfunction "2_2") (pintype "passive"))
      (node (ref "C31") (pin "2") (pinfunction "2_2") (pintype "passive"))
      (node (ref "C4") (pin "2") (pinfunction "2_2") (pintype "passive"))
      (node (ref "C9") (pin "2") (pinfunction "2_2") (pintype "passive"))
      (node (ref "D5") (pin "1") (pinfunction "Cathode_1") (pintype "passive"))
      (node (ref "D6") (pin "1") (pinfunction "Cathode_1") (pintype "passive"))
      (node (ref "FB1") (pin "1") (pinfunction "1_1") (pintype "passive"))
      (node (ref "FB2") (pin "1") (pinfunction "1_1") (pintype "passive"))
      (node (ref "FB3") (pin "1") (pinfunction "1_1") (pintype "passive"))
      (node (ref "J3") (pin "2") (pinfunction "2_2") (pintype "passive"))
      (node (ref "JP3") (pin "2") (pinfunction "2_2") (pintype "passive"))
      (node (ref "R1") (pin "2") (pinfunction "2_2") (pintype "passive"))
      (node (ref "R13") (pin "2") (pinfunction "2_2") (pintype "passive"))
      (node (ref "R14") (pin "1") (pinfunction "1_1") (pintype "passive"))
      (node (ref "R15") (pin "1") (pinfunction "1_1") (pintype "passive"))
      (node (ref "R16") (pin "1") (pinfunction "1_1") (pintype "passive"))
      (node (ref "R18") (pin "2") (pinfunction "2_2") (pintype "passive"))
      (node (ref "R2") (pin "2") (pinfunction "2_2") (pintype "passive"))
      (node (ref "R21") (pin "2") (pinfunction "2_2") (pintype "passive"))
      (node (ref "R22") (pin "2") (pinfunction "2_2") (pintype "passive"))
      (node (ref "R23") (pin "2") (pinfunction "2_2") (pintype "passive"))
      (node (ref "R27") (pin "2") (pinfunction "2_2") (pintype "passive"))
      (node (ref "R3") (pin "2") (pinfunction "2_2") (pintype "passive"))
      (node (ref "R8") (pin "2") (pinfunction "2_2") (pintype "passive"))
      (node (ref "U2") (pin "5") (pinfunction "5_5") (pintype "passive"))
      (node (ref "U4") (pin "5") (pinfunction "5_5") (pintype "passive"))
      (node (ref "U5") (pin "5") (pinfunction "5_5") (pintype "passive"))
      (node (ref "U6") (pin "5") (pinfunction "5_5") (pintype "passive"))
      (node (ref "j5") (pin "2") (pinfunction "2_2") (pintype "passive"))
      (node (ref "j7") (pin "2") (pinfunction "2_2") (pintype "passive"))
    )
    (net (code "4") (name "+AREF") (class "Default")
      (node (ref "C20") (pin "2") (pinfunction "2_2") (pintype "passive"))
      (node (ref "C25") (pin "2") (pinfunction "2_2") (pintype "passive"))
      (node (ref "J8") (pin "8") (pinfunction "8_8") (pintype "passive"))
      (node (ref "U3") (pin "21") (pinfunction "AREF_21") (pintype "passive"))
    )
    (net (code "5") (name "/+3V3_16U2_UCAP") (class "Default")
      (node (ref "C12") (pin "2") (pinfunction "2_2") (pintype "passive"))
      (node (ref "V1") (pin "27") (pinfunction "UCAP_27") (pintype "passive"))
    )
    (net (code "6") (name "/+5V_USB") (class "Default")
      (node (ref "C10") (pin "1") (pinfunction "1_1") (pintype "passive"))
      (node (ref "J6") (pin "1") (pinfunction "1_1") (pintype "passive"))
      (node (ref "L1") (pin "1") (pinfunction "1_1") (pintype "passive"))
    )
    (net (code "7") (name "/+5V{slash}3V3_16U2") (class "Default")
      (node (ref "C5") (pin "2") (pinfunction "2_2") (pintype "passive"))
      (node (ref "C6") (pin "2") (pinfunction "2_2") (pintype "passive"))
      (node (ref "C7") (pin "2") (pinfunction "2_2") (pintype "passive"))
      (node (ref "FB1") (pin "2") (pinfunction "2_2") (pintype "passive"))
      (node (ref "V1") (pin "32") (pinfunction "AVCC_32") (pintype "passive"))
      (node (ref "V1") (pin "4") (pinfunction "VCC_4") (pintype "passive"))
    )
    (net (code "8") (name "/+5V{slash}3V3_328P_AVCC") (class "Default")
      (node (ref "C23") (pin "2") (pinfunction "2_2") (pintype "passive"))
      (node (ref "C24") (pin "2") (pinfunction "2_2") (pintype "passive"))
      (node (ref "FB3") (pin "2") (pinfunction "2_2") (pintype "passive"))
      (node (ref "U3") (pin "20") (pinfunction "AVCC_20") (pintype "passive"))
    )
    (net (code "9") (name "/+5V{slash}3V3_328P_VCC") (class "Default")
      (node (ref "C21") (pin "2") (pinfunction "2_2") (pintype "passive"))
      (node (ref "C22") (pin "2") (pinfunction "2_2") (pintype "passive"))
      (node (ref "FB2") (pin "2") (pinfunction "2_2") (pintype "passive"))
      (node (ref "U3") (pin "7") (pinfunction "VCC_7") (pintype "passive"))
    )
    (net (code "10") (name "/16U2PROG_328P_RESETn") (class "Default")
      (node (ref "JP2") (pin "2") (pinfunction "2_2") (pintype "passive"))
      (node (ref "R8") (pin "1") (pinfunction "1_1") (pintype "passive"))
      (node (ref "V1") (pin "13") (pinfunction "~{HWB}_/_AIN6_/_T0_/_INT7_/_PD7_13") (pintype "passive"))
    )
    (net (code "11") (name "/16U2_16MHZ_XTAL1") (class "Default")
      (node (ref "C14") (pin "2") (pinfunction "2_2") (pintype "passive"))
      (node (ref "R9") (pin "1") (pinfunction "1_1") (pintype "passive"))
      (node (ref "V1") (pin "1") (pinfunction "XTAL1_1") (pintype "passive"))
      (node (ref "Y1") (pin "1") (pinfunction "1_1") (pintype "passive"))
    )
    (net (code "12") (name "/16U2_16MHZ_XTAL2") (class "Default")
      (node (ref "C13") (pin "2") (pinfunction "2_2") (pintype "passive"))
      (node (ref "R9") (pin "2") (pinfunction "2_2") (pintype "passive"))
      (node (ref "V1") (pin "2") (pinfunction "PC0_/_XTAL2_2") (pintype "passive"))
      (node (ref "Y1") (pin "2") (pinfunction "2_2") (pintype "passive"))
    )
    (net (code "13") (name "/16U2_BUF_RESETn") (class "Default")
      (node (ref "C29") (pin "2") (pinfunction "2_2") (pintype "passive"))
      (node (ref "R20") (pin "2") (pinfunction "2_2") (pintype "passive"))
      (node (ref "U4") (pin "1") (pinfunction "1_1") (pintype "passive"))
      (node (ref "U4") (pin "2") (pinfunction "2_2") (pintype "passive"))
    )
    (net (code "14") (name "/16U2_HDR_RESETn") (class "Default")
      (node (ref "JP1") (pin "3") (pinfunction "3_3") (pintype "passive"))
      (node (ref "j5") (pin "5") (pinfunction "5_5") (pintype "passive"))
    )
    (net (code "15") (name "/16U2_MISO") (class "Default")
      (node (ref "V1") (pin "17") (pinfunction "PDO_/_MISO_/_PCINT3_/_PB3_17") (pintype "passive"))
      (node (ref "j5") (pin "1") (pinfunction "1_1") (pintype "passive"))
    )
    (net (code "16") (name "/16U2_MOSI") (class "Default")
      (node (ref "V1") (pin "16") (pinfunction "PDI_/_MOSI_/_PCINT2_/_PB2_16") (pintype "passive"))
      (node (ref "j5") (pin "4") (pinfunction "4_4") (pintype "passive"))
    )
    (net (code "17") (name "/16U2_PB4") (class "Default")
      (node (ref "JP1") (pin "2") (pinfunction "2_2") (pintype "passive"))
      (node (ref "V1") (pin "18") (pinfunction "T1_/_PCINT4_/_PB4_18") (pintype "passive"))
      (node (ref "j4") (pin "1") (pinfunction "1_1") (pintype "passive"))
    )
    (net (code "18") (name "/16U2_PB5") (class "Default")
      (node (ref "V1") (pin "19") (pinfunction "PCINT5_/_PB5_19") (pintype "passive"))
      (node (ref "j4") (pin "3") (pinfunction "3_3") (pintype "passive"))
    )
    (net (code "19") (name "/16U2_PB6") (class "Default")
      (node (ref "V1") (pin "20") (pinfunction "PCINT6_/_PB6_20") (pintype "passive"))
      (node (ref "j4") (pin "2") (pinfunction "2_2") (pintype "passive"))
    )
    (net (code "20") (name "/16U2_PB7") (class "Default")
      (node (ref "V1") (pin "21") (pinfunction "PCINT7_/_OC.0A_/_OC.1C_/_PB7_21") (pintype "passive"))
      (node (ref "j4") (pin "4") (pinfunction "4_4") (pintype "passive"))
    )
    (net (code "21") (name "/16U2_RESETn") (class "Default")
      (node (ref "JP1") (pin "4") (pinfunction "4_4") (pintype "passive"))
      (node (ref "R3") (pin "1") (pinfunction "1_1") (pintype "passive"))
      (node (ref "U4") (pin "4") (pinfunction "4_4") (pintype "passive"))
      (node (ref "V1") (pin "24") (pinfunction "~{Rese}t_/_dW_/_PC1_24") (pintype "passive"))
    )
    (net (code "22") (name "/16U2_RX_LED") (class "Default")
      (node (ref "D2") (pin "1") (pinfunction "Cathode_1") (pintype "passive"))
      (node (ref "V1") (pin "10") (pinfunction "INT5_/_AIN3_/_PD4_10") (pintype "passive"))
    )
    (net (code "23") (name "/16U2_SCLK") (class "Default")
      (node (ref "R4") (pin "2") (pinfunction "2_2") (pintype "passive"))
      (node (ref "j5") (pin "3") (pinfunction "3_3") (pintype "passive"))
    )
    (net (code "24") (name "/16U2_TX_LED") (class "Default")
      (node (ref "D1") (pin "1") (pinfunction "Cathode_1") (pintype "passive"))
      (node (ref "V1") (pin "11") (pinfunction "XCK_AIN4_/_PCINT12_/_PD5_11") (pintype "passive"))
    )
    (net (code "25") (name "/328P RESETn") (class "Default")
      (node (ref "J3") (pin "3") (pinfunction "3_3") (pintype "passive"))
      (node (ref "JP1") (pin "1") (pinfunction "1_1") (pintype "passive"))
      (node (ref "R27") (pin "1") (pinfunction "1_1") (pintype "passive"))
      (node (ref "U3") (pin "1") (pinfunction "PC6_/_PCINT14_/_~{RESET}_1") (pintype "passive"))
      (node (ref "U6") (pin "4") (pinfunction "4_4") (pintype "passive"))
      (node (ref "j7") (pin "5") (pinfunction "5_5") (pintype "passive"))
    )
    (net (code "26") (name "/328P_16MHZ_XTAL1") (class "Default")
      (node (ref "C26") (pin "2") (pinfunction "2_2") (pintype "passive"))
      (node (ref "R19") (pin "2") (pinfunction "2_2") (pintype "passive"))
      (node (ref "U3") (pin "9") (pinfunction "PB7/PCINT7_/_XTAL2_/_TOSC2_9") (pintype "passive"))
      (node (ref "Y2") (pin "2") (pinfunction "2_2") (pintype "passive"))
    )
    (net (code "27") (name "/328P_16MHZ_XTAL2") (class "Default")
      (node (ref "C28") (pin "2") (pinfunction "2_2") (pintype "passive"))
      (node (ref "R19") (pin "1") (pinfunction "1_1") (pintype "passive"))
      (node (ref "U3") (pin "10") (pinfunction "PB7/PCINT7_/_XTAL2_/_TOSC2_10") (pintype "passive"))
      (node (ref "Y2") (pin "1") (pinfunction "1_1") (pintype "passive"))
    )
    (net (code "28") (name "/328P_AUTORESETn") (class "Default")
      (node (ref "C15") (pin "1") (pinfunction "1_1") (pintype "passive"))
      (node (ref "R23") (pin "1") (pinfunction "1_1") (pintype "passive"))
      (node (ref "U6") (pin "1") (pinfunction "1_1") (pintype "passive"))
    )
    (net (code "29") (name "/328P_BUF_RESETn") (class "Default")
      (node (ref "C33") (pin "2") (pinfunction "2_2") (pintype "passive"))
      (node (ref "R26") (pin "2") (pinfunction "2_2") (pintype "passive"))
      (node (ref "U6") (pin "2") (pinfunction "2_2") (pintype "passive"))
    )
    (net (code "30") (name "/AD0") (class "Default")
      (node (ref "J9") (pin "1") (pinfunction "1_1") (pintype "passive"))
      (node (ref "U3") (pin "23") (pinfunction "ADC0_/_PCINT8_/_PC0_23") (pintype "passive"))
    )
    (net (code "31") (name "/AD1") (class "Default")
      (node (ref "J9") (pin "2") (pinfunction "2_2") (pintype "passive"))
      (node (ref "U3") (pin "24") (pinfunction "ADC1_/_PCINT9_/_PC1_24") (pintype "passive"))
    )
    (net (code "32") (name "/AD2") (class "Default")
      (node (ref "J9") (pin "3") (pinfunction "3_3") (pintype "passive"))
      (node (ref "U3") (pin "25") (pinfunction "ADC2_/_PCINT10_/_PC2_25") (pintype "passive"))
    )
    (net (code "33") (name "/AD3") (class "Default")
      (node (ref "J9") (pin "4") (pinfunction "4_4") (pintype "passive"))
      (node (ref "U3") (pin "26") (pinfunction "ADC3_/_PCINT11_/_PC3_26") (pintype "passive"))
    )
    (net (code "34") (name "/AD4{slash}SDA") (class "Default")
      (node (ref "J8") (pin "9") (pinfunction "9_9") (pintype "passive"))
      (node (ref "J9") (pin "5") (pinfunction "5_5") (pintype "passive"))
      (node (ref "U3") (pin "27") (pinfunction "ADC4/_SDA_/_PCINT12_/_PC4_27") (pintype "passive"))
    )
    (net (code "35") (name "/AD5{slash}SCL") (class "Default")
      (node (ref "J8") (pin "10") (pinfunction "10_10") (pintype "passive"))
      (node (ref "J9") (pin "6") (pinfunction "6_6") (pintype "passive"))
      (node (ref "U3") (pin "28") (pinfunction "ADC5_/_SCL_/_PCINT13_/_PC5_28") (pintype "passive"))
    )
    (net (code "36") (name "/BUTTON_RESETn") (class "Default")
      (node (ref "D6") (pin "2") (pinfunction "Anode_2") (pintype "passive"))
      (node (ref "R22") (pin "1") (pinfunction "1_1") (pintype "passive"))
      (node (ref "R26") (pin "1") (pinfunction "1_1") (pintype "passive"))
      (node (ref "SW2") (pin "1") (pinfunction "1_1") (pintype "passive"))
      (node (ref "SW2") (pin "2") (pinfunction "2_2") (pintype "passive"))
    )
    (net (code "37") (name "/CON_USB_N") (class "Default")
      (node (ref "J6") (pin "2") (pinfunction "2_2") (pintype "passive"))
      (node (ref "R5") (pin "1") (pinfunction "1_1") (pintype "passive"))
      (node (ref "V2") (pin "2") (pinfunction "2_2") (pintype "passive"))
    )
    (net (code "38") (name "/CON_USB_P") (class "Default")
      (node (ref "J6") (pin "3") (pinfunction "3_3") (pintype "passive"))
      (node (ref "R6") (pin "1") (pinfunction "1_1") (pintype "passive"))
      (node (ref "V3") (pin "2") (pinfunction "2_2") (pintype "passive"))
    )
    (net (code "39") (name "/IO0") (class "Default")
      (node (ref "J10") (pin "1") (pinfunction "1_1") (pintype "passive"))
      (node (ref "R10") (pin "2") (pinfunction "2_2") (pintype "passive"))
      (node (ref "U3") (pin "2") (pinfunction "RXD_/_PCINT16__/_PD0_2") (pintype "passive"))
    )
    (net (code "40") (name "/IO1") (class "Default")
      (node (ref "J10") (pin "2") (pinfunction "2_2") (pintype "passive"))
      (node (ref "R11") (pin "2") (pinfunction "2_2") (pintype "passive"))
      (node (ref "U3") (pin "3") (pinfunction "TXD_/_PCINT17_/_PD1_3") (pintype "passive"))
    )
    (net (code "41") (name "/IO2") (class "Default")
      (node (ref "J10") (pin "3") (pinfunction "3_3") (pintype "passive"))
      (node (ref "U3") (pin "4") (pinfunction "INT0_/_PCINT18_/_PD2_4") (pintype "passive"))
    )
    (net (code "42") (name "/IO3") (class "Default")
      (node (ref "J10") (pin "4") (pinfunction "4_4") (pintype "passive"))
      (node (ref "U3") (pin "5") (pinfunction "OC2B_/_INT1/_PCINT19/_PD3_5") (pintype "passive"))
    )
    (net (code "43") (name "/IO4") (class "Default")
      (node (ref "J10") (pin "5") (pinfunction "5_5") (pintype "passive"))
      (node (ref "U3") (pin "6") (pinfunction "XCK/_T0_/PCINT20/_PD4_6") (pintype "passive"))
    )
    (net (code "44") (name "/IO5") (class "Default")
      (node (ref "J10") (pin "6") (pinfunction "6_6") (pintype "passive"))
      (node (ref "U3") (pin "11") (pinfunction "PD5/PCINT21/OC0B/T1)_11") (pintype "passive"))
    )
    (net (code "45") (name "/IO6") (class "Default")
      (node (ref "J10") (pin "7") (pinfunction "7_7") (pintype "passive"))
      (node (ref "U3") (pin "12") (pinfunction "PD6/PCINT22/OC0A/AIN0_12") (pintype "passive"))
    )
    (net (code "46") (name "/IO7") (class "Default")
      (node (ref "J10") (pin "8") (pinfunction "8_8") (pintype "passive"))
      (node (ref "U3") (pin "13") (pinfunction "PD7/PCINT23/AIN1)_13") (pintype "passive"))
    )
    (net (code "47") (name "/IO8") (class "Default")
      (node (ref "J8") (pin "1") (pinfunction "1_1") (pintype "passive"))
      (node (ref "R24") (pin "2") (pinfunction "2_2") (pintype "passive"))
      (node (ref "U3") (pin "14") (pinfunction "CLKO_/_ICP1_/_PCINT0/_PB0_14") (pintype "passive"))
    )
    (net (code "48") (name "/IO9") (class "Default")
      (node (ref "J8") (pin "2") (pinfunction "2_2") (pintype "passive"))
      (node (ref "U3") (pin "15") (pinfunction "OC1A_/_PCINT1_/_PB1_15") (pintype "passive"))
    )
    (net (code "49") (name "/MISO") (class "Default")
      (node (ref "J8") (pin "5") (pinfunction "5_5") (pintype "passive"))
      (node (ref "U3") (pin "18") (pinfunction "MISO_/_PCINT4_/_PB4_18") (pintype "passive"))
      (node (ref "j7") (pin "1") (pinfunction "1_1") (pintype "passive"))
    )
    (net (code "50") (name "/MOSI") (class "Default")
      (node (ref "J8") (pin "4") (pinfunction "4_4") (pintype "passive"))
      (node (ref "U3") (pin "17") (pinfunction "MOSI/_OC2A_/_PCINT3_/_PB3_17") (pintype "passive"))
      (node (ref "j7") (pin "4") (pinfunction "4_4") (pintype "passive"))
    )
    (net (code "51") (name "/SCK") (class "Default")
      (node (ref "R17") (pin "1") (pinfunction "1_1") (pintype "passive"))
      (node (ref "U2") (pin "1") (pinfunction "1_1") (pintype "passive"))
      (node (ref "U2") (pin "2") (pinfunction "2_2") (pintype "passive"))
      (node (ref "U3") (pin "19") (pinfunction "SCK_/_PCINT5_/_PB5_19") (pintype "passive"))
    )
    (net (code "52") (name "/SCK_HDR") (class "Default")
      (node (ref "J8") (pin "6") (pinfunction "6_6") (pintype "passive"))
      (node (ref "R17") (pin "2") (pinfunction "2_2") (pintype "passive"))
      (node (ref "j7") (pin "3") (pinfunction "3_3") (pintype "passive"))
    )
    (net (code "53") (name "/SS") (class "Default")
      (node (ref "J8") (pin "3") (pinfunction "3_3") (pintype "passive"))
      (node (ref "U3") (pin "16") (pinfunction "~{S}S_/_OC1B_/_PCINT2_/_PB2_16") (pintype "passive"))
    )
    (net (code "54") (name "/USB_N") (class "Default")
      (node (ref "R5") (pin "2") (pinfunction "2_2") (pintype "passive"))
      (node (ref "V1") (pin "30") (pinfunction "D-_30") (pintype "passive"))
    )
    (net (code "55") (name "/USB_P") (class "Default")
      (node (ref "R6") (pin "2") (pinfunction "2_2") (pintype "passive"))
      (node (ref "V1") (pin "29") (pinfunction "D+_29") (pintype "passive"))
    )
    (net (code "56") (name "/USER_BUTTON") (class "Default")
      (node (ref "R21") (pin "1") (pinfunction "1_1") (pintype "passive"))
      (node (ref "R25") (pin "1") (pinfunction "1_1") (pintype "passive"))
      (node (ref "SW1") (pin "1") (pinfunction "1_1") (pintype "passive"))
      (node (ref "SW1") (pin "2") (pinfunction "2_2") (pintype "passive"))
    )
    (net (code "57") (name "/USER_BUTTON_BUF") (class "Default")
      (node (ref "C32") (pin "2") (pinfunction "2_2") (pintype "passive"))
      (node (ref "R25") (pin "2") (pinfunction "2_2") (pintype "passive"))
      (node (ref "U5") (pin "1") (pinfunction "1_1") (pintype "passive"))
      (node (ref "U5") (pin "2") (pinfunction "2_2") (pintype "passive"))
    )
    (net (code "58") (name "GND") (class "Default")
      (node (ref "C1") (pin "1") (pinfunction "1_1") (pintype "passive"))
      (node (ref "C10") (pin "2") (pinfunction "2_2") (pintype "passive"))
      (node (ref "C11") (pin "2") (pinfunction "2_2") (pintype "passive"))
      (node (ref "C12") (pin "1") (pinfunction "1_1") (pintype "passive"))
      (node (ref "C13") (pin "1") (pinfunction "1_1") (pintype "passive"))
      (node (ref "C14") (pin "1") (pinfunction "1_1") (pintype "passive"))
      (node (ref "C16") (pin "1") (pinfunction "1_1") (pintype "passive"))
      (node (ref "C17") (pin "1") (pinfunction "1_1") (pintype "passive"))
      (node (ref "C18") (pin "1") (pinfunction "1_1") (pintype "passive"))
      (node (ref "C19") (pin "1") (pinfunction "1_1") (pintype "passive"))
      (node (ref "C2") (pin "1") (pinfunction "1_1") (pintype "passive"))
      (node (ref "C20") (pin "1") (pinfunction "1_1") (pintype "passive"))
      (node (ref "C21") (pin "1") (pinfunction "1_1") (pintype "passive"))
      (node (ref "C22") (pin "1") (pinfunction "1_1") (pintype "passive"))
      (node (ref "C23") (pin "1") (pinfunction "1_1") (pintype "passive"))
      (node (ref "C24") (pin "1") (pinfunction "1_1") (pintype "passive"))
      (node (ref "C25") (pin "1") (pinfunction "1_1") (pintype "passive"))
      (node (ref "C26") (pin "1") (pinfunction "1_1") (pintype "passive"))
      (node (ref "C27") (pin "1") (pinfunction "1_1") (pintype "passive"))
      (node (ref "C28") (pin "1") (pinfunction "1_1") (pintype "passive"))
      (node (ref "C29") (pin "1") (pinfunction "1_1") (pintype "passive"))
      (node (ref "C3") (pin "1") (pinfunction "1_1") (pintype "passive"))
      (node (ref "C30") (pin "1") (pinfunction "1_1") (pintype "passive"))
      (node (ref "C31") (pin "1") (pinfunction "1_1") (pintype "passive"))
      (node (ref "C32") (pin "1") (pinfunction "1_1") (pintype "passive"))
      (node (ref "C33") (pin "1") (pinfunction "1_1") (pintype "passive"))
      (node (ref "C4") (pin "1") (pinfunction "1_1") (pintype "passive"))
      (node (ref "C5") (pin "1") (pinfunction "1_1") (pintype "passive"))
      (node (ref "C6") (pin "1") (pinfunction "1_1") (pintype "passive"))
      (node (ref "C7") (pin "1") (pinfunction "1_1") (pintype "passive"))
      (node (ref "C8") (pin "1") (pinfunction "1_1") (pintype "passive"))
      (node (ref "C9") (pin "1") (pinfunction "1_1") (pintype "passive"))
      (node (ref "D3") (pin "1") (pinfunction "Cathode_1") (pintype "passive"))
      (node (ref "J2") (pin "1") (pinfunction "_1_1") (pintype "passive"))
      (node (ref "J3") (pin "6") (pinfunction "6_6") (pintype "passive"))
      (node (ref "J3") (pin "7") (pinfunction "7_7") (pintype "passive"))
      (node (ref "J6") (pin "10") (pinfunction "10_10") (pintype "passive"))
      (node (ref "J6") (pin "11") (pinfunction "11_11") (pintype "passive"))
      (node (ref "J6") (pin "5") (pinfunction "5_5") (pintype "passive"))
      (node (ref "J6") (pin "6") (pinfunction "6_6") (pintype "passive"))
      (node (ref "J6") (pin "7") (pinfunction "7_7") (pintype "passive"))
      (node (ref "J6") (pin "8") (pinfunction "8_8") (pintype "passive"))
      (node (ref "J6") (pin "9") (pinfunction "9_9") (pintype "passive"))
      (node (ref "J8") (pin "7") (pinfunction "7_7") (pintype "passive"))
      (node (ref "MH2") (pin "1") (pinfunction "1_1") (pintype "passive"))
      (node (ref "MH3") (pin "1") (pinfunction "1_1") (pintype "passive"))
      (node (ref "MH4") (pin "1") (pinfunction "1_1") (pintype "passive"))
      (node (ref "R12") (pin "1") (pinfunction "1_1") (pintype "passive"))
      (node (ref "R7") (pin "2") (pinfunction "2_2") (pintype "passive"))
      (node (ref "SW1") (pin "3") (pinfunction "3_3") (pintype "passive"))
      (node (ref "SW1") (pin "4") (pinfunction "4_4") (pintype "passive"))
      (node (ref "SW2") (pin "3") (pinfunction "3_3") (pintype "passive"))
      (node (ref "SW2") (pin "4") (pinfunction "4_4") (pintype "passive"))
      (node (ref "U1") (pin "3") (pinfunction "GND_3") (pintype "passive"))
      (node (ref "U1") (pin "6") (pinfunction "EPAD_6") (pintype "passive"))
      (node (ref "U2") (pin "3") (pinfunction "3_3") (pintype "passive"))
      (node (ref "U3") (pin "22") (pinfunction "GND_22") (pintype "passive"))
      (node (ref "U3") (pin "8") (pinfunction "GND_8") (pintype "passive"))
      (node (ref "U4") (pin "3") (pinfunction "3_3") (pintype "passive"))
      (node (ref "U5") (pin "3") (pinfunction "3_3") (pintype "passive"))
      (node (ref "U6") (pin "3") (pinfunction "3_3") (pintype "passive"))
      (node (ref "V1") (pin "28") (pinfunction "UGND_28") (pintype "passive"))
      (node (ref "V1") (pin "3") (pinfunction "GND_3") (pintype "passive"))
      (node (ref "V2") (pin "1") (pinfunction "1_1") (pintype "passive"))
      (node (ref "V3") (pin "1") (pinfunction "1_1") (pintype "passive"))
      (node (ref "j5") (pin "6") (pinfunction "6_6") (pintype "passive"))
      (node (ref "j7") (pin "6") (pinfunction "6_6") (pintype "passive"))
    )
    (net (code "59") (name "Net-(C15-Pad2)") (class "Default")
      (node (ref "C15") (pin "2") (pinfunction "2_2") (pintype "passive"))
      (node (ref "JP2") (pin "1") (pinfunction "1_1") (pintype "passive"))
    )
    (net (code "60") (name "Net-(D1-Anode)") (class "Default")
      (node (ref "D1") (pin "2") (pinfunction "Anode_2") (pintype "passive"))
      (node (ref "R1") (pin "1") (pinfunction "1_1") (pintype "passive"))
    )
    (net (code "61") (name "Net-(D2-Anode)") (class "Default")
      (node (ref "D2") (pin "2") (pinfunction "Anode_2") (pintype "passive"))
      (node (ref "R2") (pin "1") (pinfunction "1_1") (pintype "passive"))
    )
    (net (code "62") (name "Net-(D3-Anode)") (class "Default")
      (node (ref "D3") (pin "2") (pinfunction "Anode_2") (pintype "passive"))
      (node (ref "R16") (pin "2") (pinfunction "2_2") (pintype "passive"))
    )
    (net (code "63") (name "Net-(D4-Anode)") (class "Default")
      (node (ref "D4") (pin "2") (pinfunction "Anode_2") (pintype "passive"))
      (node (ref "R15") (pin "2") (pinfunction "2_2") (pintype "passive"))
    )
    (net (code "64") (name "Net-(D4-Cathode)") (class "Default")
      (node (ref "D4") (pin "1") (pinfunction "Cathode_1") (pintype "passive"))
      (node (ref "U2") (pin "4") (pinfunction "4_4") (pintype "passive"))
    )
    (net (code "65") (name "Net-(D5-Anode)") (class "Default")
      (node (ref "D5") (pin "2") (pinfunction "Anode_2") (pintype "passive"))
      (node (ref "R18") (pin "1") (pinfunction "1_1") (pintype "passive"))
      (node (ref "R20") (pin "1") (pinfunction "1_1") (pintype "passive"))
    )
    (net (code "66") (name "Net-(J6-Pad4)") (class "Default")
      (node (ref "J6") (pin "4") (pinfunction "4_4") (pintype "passive"))
      (node (ref "R7") (pin "1") (pinfunction "1_1") (pintype "passive"))
    )
    (net (code "67") (name "Net-(JP2-Pad3)") (class "Default")
      (node (ref "JP2") (pin "3") (pinfunction "3_3") (pintype "passive"))
      (node (ref "R12") (pin "2") (pinfunction "2_2") (pintype "passive"))
    )
    (net (code "68") (name "Net-(R24-Pad1)") (class "Default")
      (node (ref "R24") (pin "1") (pinfunction "1_1") (pintype "passive"))
      (node (ref "U5") (pin "4") (pinfunction "4_4") (pintype "passive"))
    )
    (net (code "69") (name "Net-(V1-RXD1_{slash}_AIN1_{slash}_INT2)_PD2)") (class "Default")
      (node (ref "R11") (pin "1") (pinfunction "1_1") (pintype "passive"))
      (node (ref "V1") (pin "8") (pinfunction "RXD1_/_AIN1_/_INT2)_PD2_8") (pintype "passive"))
    )
    (net (code "70") (name "Net-(V1-SCLK_{slash}_PCINT1_{slash}_PB1)") (class "Default")
      (node (ref "R4") (pin "1") (pinfunction "1_1") (pintype "passive"))
      (node (ref "V1") (pin "15") (pinfunction "SCLK_/_PCINT1_/_PB1_15") (pintype "passive"))
    )
    (net (code "71") (name "Net-(V1-TXD1_{slash}_INT3_{slash}_PD3)") (class "Default")
      (node (ref "R10") (pin "1") (pinfunction "1_1") (pintype "passive"))
      (node (ref "V1") (pin "9") (pinfunction "TXD1_/_INT3_/_PD3_9") (pintype "passive"))
    )
    (net (code "72") (name "unconnected-(J3-Pad1)") (class "Default")
      (node (ref "J3") (pin "1") (pinfunction "1_1") (pintype "passive+no_connect"))
    )
    (net (code "73") (name "unconnected-(J3-Pad8)") (class "Default")
      (node (ref "J3") (pin "8") (pinfunction "8_8") (pintype "passive+no_connect"))
    )
    (net (code "74") (name "unconnected-(MH1-Pad1)") (class "Default")
      (node (ref "MH1") (pin "1") (pinfunction "1_1") (pintype "passive+no_connect"))
    )
    (net (code "75") (name "unconnected-(V1-AIN0_{slash}_INT1_{slash}_PD1-Pad7)") (class "Default")
      (node (ref "V1") (pin "7") (pinfunction "AIN0_/_INT1_/_PD1_7") (pintype "passive+no_connect"))
    )
    (net (code "76") (name "unconnected-(V1-INT4_{slash}_ICP1_{slash}_CLKO_{slash}PC7-Pad22)") (class "Default")
      (node (ref "V1") (pin "22") (pinfunction "INT4_/_ICP1_/_CLKO_/PC7_22") (pintype "passive+no_connect"))
    )
    (net (code "77") (name "unconnected-(V1-OC.0B_{slash}_INT0_{slash}_PD0-Pad6)") (class "Default")
      (node (ref "V1") (pin "6") (pinfunction "OC.0B_/_INT0_/_PD0_6") (pintype "passive+no_connect"))
    )
    (net (code "78") (name "unconnected-(V1-OC.1A_{slash}_PCINT8_{slash}_PC6-Pad23)") (class "Default")
      (node (ref "V1") (pin "23") (pinfunction "OC.1A_/_PCINT8_/_PC6_23") (pintype "passive+no_connect"))
    )
    (net (code "79") (name "unconnected-(V1-PCINT9_{slash}_OC.1B_{slash}_PC5-Pad25)") (class "Default")
      (node (ref "V1") (pin "25") (pinfunction "PCINT9_/_OC.1B_/_PC5_25") (pintype "passive+no_connect"))
    )
    (net (code "80") (name "unconnected-(V1-PCINT10_{slash}_PC4-Pad26)") (class "Default")
      (node (ref "V1") (pin "26") (pinfunction "PCINT10_/_PC4_26") (pintype "passive+no_connect"))
    )
    (net (code "81") (name "unconnected-(V1-PCINT11_{slash}_AIN2_{slash}_PC2-Pad5)") (class "Default")
      (node (ref "V1") (pin "5") (pinfunction "PCINT11_/_AIN2_/_PC2_5") (pintype "passive+no_connect"))
    )
    (net (code "82") (name "unconnected-(V1-~{RT}S_{slash}_AIN5_{slash}_INT6_{slash}__PD6-Pad12)") (class "Default")
      (node (ref "V1") (pin "12") (pinfunction "~{RT}S_/_AIN5_/_INT6_/__PD6_12") (pintype "passive+no_connect"))
    )
    (net (code "83") (name "unconnected-(V1-~{SS}_{slash}_PCINT0_{slash}_PB0-Pad14)") (class "Default")
      (node (ref "V1") (pin "14") (pinfunction "~{SS}_/_PCINT0_/_PB0_14") (pintype "passive+no_connect"))
    )
  )
)
